# 0_TO_9_Counter_74LS90.net
KiCad netlist of a schematic drawn in EAGLE
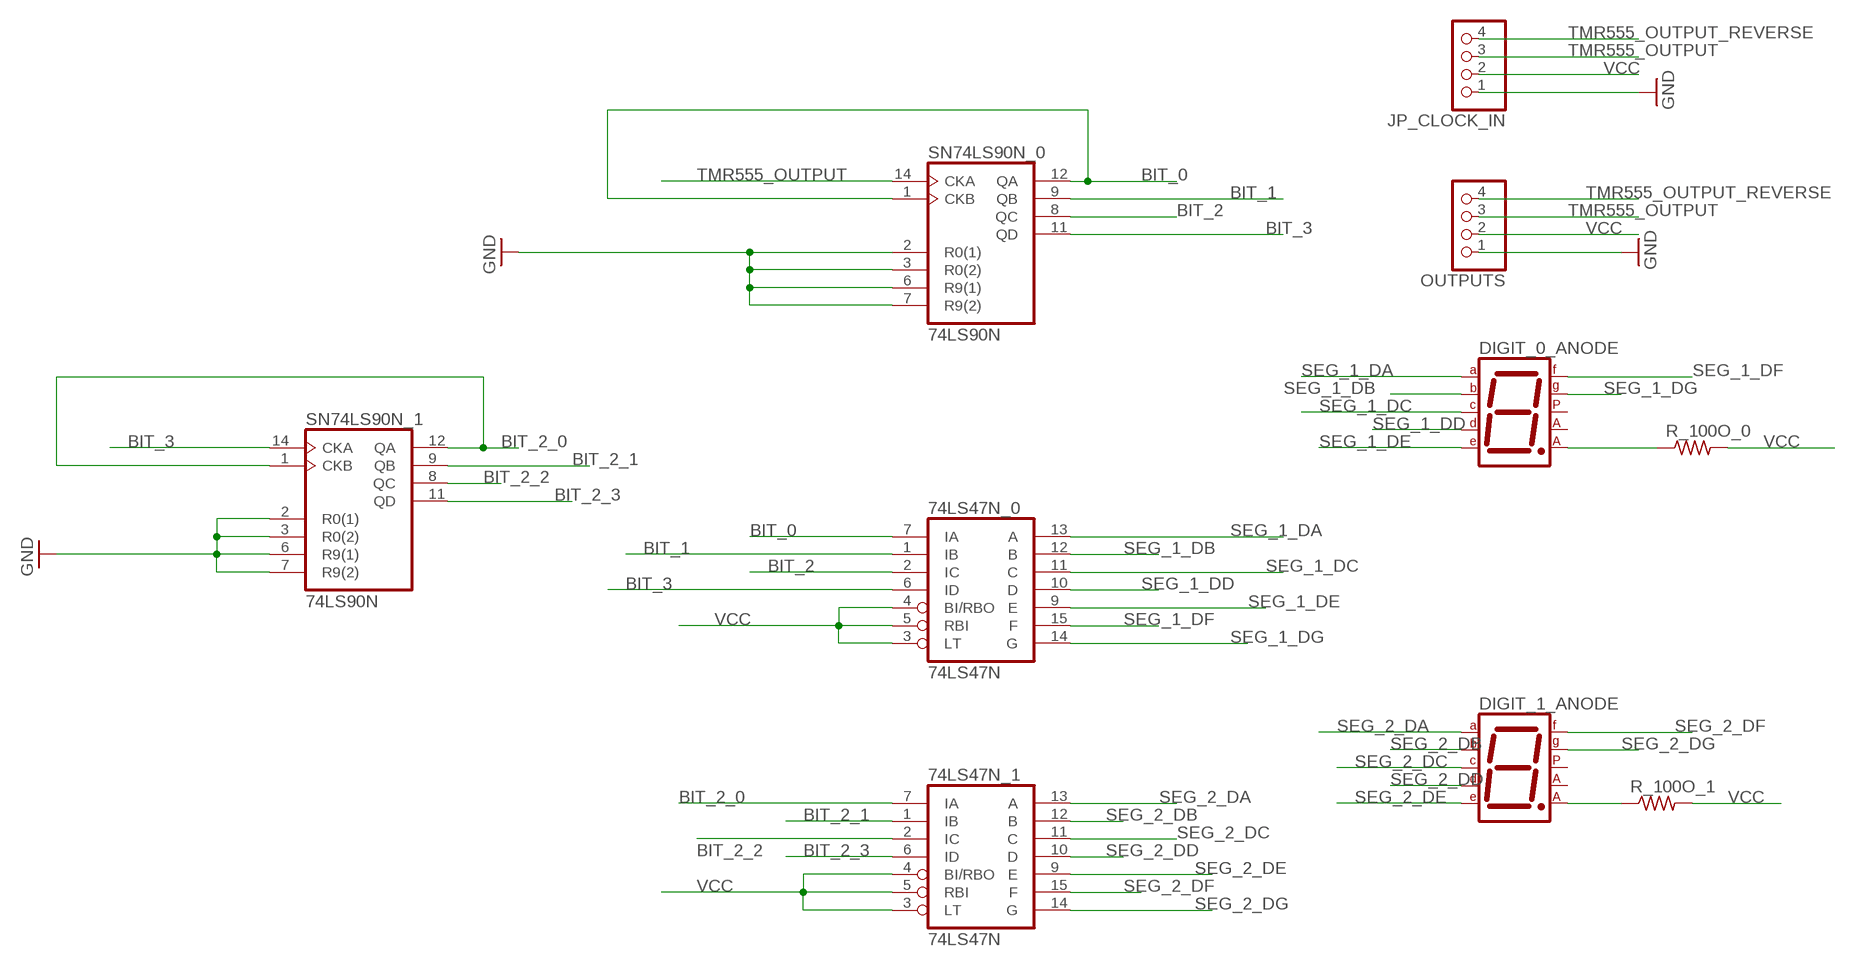
[diagram p0: schematic, sheet 1]

(export (version "E")
  (design (tool "Eeschema 10.0.6"))
  (components
    (comp (ref "74LS47N_0")
      (value "74LS47N")
      (footprint "eagle-import:DIL16")
      (libsource (lib "eagle-import") (part "7447NLS"))
    )
    (comp (ref "74LS47N_1")
      (value "74LS47N")
      (footprint "eagle-import:DIL16")
      (libsource (lib "eagle-import") (part "7447NLS"))
    )
    (comp (ref "DIGIT_0_ANODE")
      (value "7SEG-CA")
      (footprint "eagle-import:7SEG-13")
      (libsource (lib "eagle-import") (part "7SEG-CA"))
    )
    (comp (ref "DIGIT_1_ANODE")
      (value "7SEG-CA")
      (footprint "eagle-import:7SEG-13")
      (libsource (lib "eagle-import") (part "7SEG-CA"))
    )
    (comp (ref "JP_CLOCK_IN")
      (value "PINHD-1X4")
      (footprint "eagle-import:1X04")
      (libsource (lib "eagle-import") (part "PINHD-1X4"))
    )
    (comp (ref "OUTPUTS")
      (value "PINHD-1X4")
      (footprint "eagle-import:1X04")
      (libsource (lib "eagle-import") (part "PINHD-1X4"))
    )
    (comp (ref "R_100O_0")
      (value "R-US_R1206")
      (footprint "eagle-import:R1206")
      (libsource (lib "eagle-import") (part "R-US_R1206"))
    )
    (comp (ref "R_100O_1")
      (value "R-US_R1206")
      (footprint "eagle-import:R1206")
      (libsource (lib "eagle-import") (part "R-US_R1206"))
    )
    (comp (ref "SN74LS90N_0")
      (value "74LS90N")
      (footprint "eagle-import:DIL14")
      (libsource (lib "eagle-import") (part "7490NLS"))
    )
    (comp (ref "SN74LS90N_1")
      (value "74LS90N")
      (footprint "eagle-import:DIL14")
      (libsource (lib "eagle-import") (part "7490NLS"))
    )
  )
  (nets
    (net (code "1") (name "/BIT_0") (class "Default")
      (node (ref "74LS47N_0") (pin "7") (pinfunction "IA_7") (pintype "input"))
      (node (ref "SN74LS90N_0") (pin "1") (pinfunction "CKB_1") (pintype "input"))
      (node (ref "SN74LS90N_0") (pin "12") (pinfunction "QA_12") (pintype "output"))
    )
    (net (code "2") (name "/BIT_1") (class "Default")
      (node (ref "74LS47N_0") (pin "1") (pinfunction "IB_1") (pintype "input"))
      (node (ref "SN74LS90N_0") (pin "9") (pinfunction "QB_9") (pintype "output"))
    )
    (net (code "3") (name "/BIT_2") (class "Default")
      (node (ref "74LS47N_0") (pin "2") (pinfunction "IC_2") (pintype "input"))
      (node (ref "SN74LS90N_0") (pin "8") (pinfunction "QC_8") (pintype "output"))
    )
    (net (code "4") (name "/BIT_2_0") (class "Default")
      (node (ref "74LS47N_1") (pin "7") (pinfunction "IA_7") (pintype "input"))
      (node (ref "SN74LS90N_1") (pin "1") (pinfunction "CKB_1") (pintype "input"))
      (node (ref "SN74LS90N_1") (pin "12") (pinfunction "QA_12") (pintype "output"))
    )
    (net (code "5") (name "/BIT_2_1") (class "Default")
      (node (ref "74LS47N_1") (pin "1") (pinfunction "IB_1") (pintype "input"))
      (node (ref "SN74LS90N_1") (pin "9") (pinfunction "QB_9") (pintype "output"))
    )
    (net (code "6") (name "/BIT_2_2") (class "Default")
      (node (ref "74LS47N_1") (pin "2") (pinfunction "IC_2") (pintype "input"))
      (node (ref "SN74LS90N_1") (pin "8") (pinfunction "QC_8") (pintype "output"))
    )
    (net (code "7") (name "/BIT_2_3") (class "Default")
      (node (ref "74LS47N_1") (pin "6") (pinfunction "ID_6") (pintype "input"))
      (node (ref "SN74LS90N_1") (pin "11") (pinfunction "QD_11") (pintype "output"))
    )
    (net (code "8") (name "/BIT_3") (class "Default")
      (node (ref "74LS47N_0") (pin "6") (pinfunction "ID_6") (pintype "input"))
      (node (ref "SN74LS90N_0") (pin "11") (pinfunction "QD_11") (pintype "output"))
      (node (ref "SN74LS90N_1") (pin "14") (pinfunction "CKA_14") (pintype "input"))
    )
    (net (code "9") (name "/SEG_1_DA") (class "Default")
      (node (ref "74LS47N_0") (pin "13") (pinfunction "A_13") (pintype "output"))
      (node (ref "DIGIT_0_ANODE") (pin "7") (pinfunction "A_7") (pintype "passive"))
    )
    (net (code "10") (name "/SEG_1_DB") (class "Default")
      (node (ref "74LS47N_0") (pin "12") (pinfunction "B_12") (pintype "output"))
      (node (ref "DIGIT_0_ANODE") (pin "6") (pinfunction "B_6") (pintype "passive"))
    )
    (net (code "11") (name "/SEG_1_DC") (class "Default")
      (node (ref "74LS47N_0") (pin "11") (pinfunction "C_11") (pintype "output"))
      (node (ref "DIGIT_0_ANODE") (pin "4") (pinfunction "C_4") (pintype "passive"))
    )
    (net (code "12") (name "/SEG_1_DD") (class "Default")
      (node (ref "74LS47N_0") (pin "10") (pinfunction "D_10") (pintype "output"))
      (node (ref "DIGIT_0_ANODE") (pin "2") (pinfunction "D_2") (pintype "passive"))
    )
    (net (code "13") (name "/SEG_1_DE") (class "Default")
      (node (ref "74LS47N_0") (pin "9") (pinfunction "E_9") (pintype "output"))
      (node (ref "DIGIT_0_ANODE") (pin "1") (pinfunction "E_1") (pintype "passive"))
    )
    (net (code "14") (name "/SEG_1_DF") (class "Default")
      (node (ref "74LS47N_0") (pin "15") (pinfunction "F_15") (pintype "output"))
      (node (ref "DIGIT_0_ANODE") (pin "9") (pinfunction "F_9") (pintype "passive"))
    )
    (net (code "15") (name "/SEG_1_DG") (class "Default")
      (node (ref "74LS47N_0") (pin "14") (pinfunction "G_14") (pintype "output"))
      (node (ref "DIGIT_0_ANODE") (pin "10") (pinfunction "G_10") (pintype "passive"))
    )
    (net (code "16") (name "/SEG_2_DA") (class "Default")
      (node (ref "74LS47N_1") (pin "13") (pinfunction "A_13") (pintype "output"))
      (node (ref "DIGIT_1_ANODE") (pin "7") (pinfunction "A_7") (pintype "passive"))
    )
    (net (code "17") (name "/SEG_2_DB") (class "Default")
      (node (ref "74LS47N_1") (pin "12") (pinfunction "B_12") (pintype "output"))
      (node (ref "DIGIT_1_ANODE") (pin "6") (pinfunction "B_6") (pintype "passive"))
    )
    (net (code "18") (name "/SEG_2_DC") (class "Default")
      (node (ref "74LS47N_1") (pin "11") (pinfunction "C_11") (pintype "output"))
      (node (ref "DIGIT_1_ANODE") (pin "4") (pinfunction "C_4") (pintype "passive"))
    )
    (net (code "19") (name "/SEG_2_DD") (class "Default")
      (node (ref "74LS47N_1") (pin "10") (pinfunction "D_10") (pintype "output"))
      (node (ref "DIGIT_1_ANODE") (pin "2") (pinfunction "D_2") (pintype "passive"))
    )
    (net (code "20") (name "/SEG_2_DE") (class "Default")
      (node (ref "74LS47N_1") (pin "9") (pinfunction "E_9") (pintype "output"))
      (node (ref "DIGIT_1_ANODE") (pin "1") (pinfunction "E_1") (pintype "passive"))
    )
    (net (code "21") (name "/SEG_2_DF") (class "Default")
      (node (ref "74LS47N_1") (pin "15") (pinfunction "F_15") (pintype "output"))
      (node (ref "DIGIT_1_ANODE") (pin "9") (pinfunction "F_9") (pintype "passive"))
    )
    (net (code "22") (name "/SEG_2_DG") (class "Default")
      (node (ref "74LS47N_1") (pin "14") (pinfunction "G_14") (pintype "output"))
      (node (ref "DIGIT_1_ANODE") (pin "10") (pinfunction "G_10") (pintype "passive"))
    )
    (net (code "23") (name "/TMR555_OUTPUT") (class "Default")
      (node (ref "JP_CLOCK_IN") (pin "3") (pinfunction "3_3") (pintype "passive"))
      (node (ref "OUTPUTS") (pin "3") (pinfunction "3_3") (pintype "passive"))
      (node (ref "SN74LS90N_0") (pin "14") (pinfunction "CKA_14") (pintype "input"))
    )
    (net (code "24") (name "/TMR555_OUTPUT_REVERSE") (class "Default")
      (node (ref "JP_CLOCK_IN") (pin "4") (pinfunction "4_4") (pintype "passive"))
      (node (ref "OUTPUTS") (pin "4") (pinfunction "4_4") (pintype "passive"))
    )
    (net (code "25") (name "/VCC") (class "Default")
      (node (ref "74LS47N_0") (pin "3") (pinfunction "LT_3") (pintype "input"))
      (node (ref "74LS47N_0") (pin "4") (pinfunction "BI/RBO_4") (pintype "input"))
      (node (ref "74LS47N_0") (pin "5") (pinfunction "RBI_5") (pintype "input"))
      (node (ref "74LS47N_1") (pin "3") (pinfunction "LT_3") (pintype "input"))
      (node (ref "74LS47N_1") (pin "4") (pinfunction "BI/RBO_4") (pintype "input"))
      (node (ref "74LS47N_1") (pin "5") (pinfunction "RBI_5") (pintype "input"))
      (node (ref "JP_CLOCK_IN") (pin "2") (pinfunction "2_2") (pintype "passive"))
      (node (ref "OUTPUTS") (pin "2") (pinfunction "2_2") (pintype "passive"))
      (node (ref "R_100O_0") (pin "2") (pinfunction "2_2") (pintype "passive"))
      (node (ref "R_100O_1") (pin "2") (pinfunction "2_2") (pintype "passive"))
    )
    (net (code "26") (name "GND") (class "Default")
      (node (ref "JP_CLOCK_IN") (pin "1") (pinfunction "1_1") (pintype "passive"))
      (node (ref "OUTPUTS") (pin "1") (pinfunction "1_1") (pintype "passive"))
      (node (ref "SN74LS90N_0") (pin "2") (pinfunction "R0(1)_2") (pintype "input"))
      (node (ref "SN74LS90N_0") (pin "3") (pinfunction "R0(2)_3") (pintype "input"))
      (node (ref "SN74LS90N_0") (pin "6") (pinfunction "R9(1)_6") (pintype "input"))
      (node (ref "SN74LS90N_0") (pin "7") (pinfunction "R9(2)_7") (pintype "input"))
      (node (ref "SN74LS90N_1") (pin "2") (pinfunction "R0(1)_2") (pintype "input"))
      (node (ref "SN74LS90N_1") (pin "3") (pinfunction "R0(2)_3") (pintype "input"))
      (node (ref "SN74LS90N_1") (pin "6") (pinfunction "R9(1)_6") (pintype "input"))
      (node (ref "SN74LS90N_1") (pin "7") (pinfunction "R9(2)_7") (pintype "input"))
    )
    (net (code "27") (name "Net-(DIGIT_0_ANODE-CA2)") (class "Default")
      (node (ref "DIGIT_0_ANODE") (pin "8") (pinfunction "CA2_8") (pintype "passive"))
      (node (ref "R_100O_0") (pin "1") (pinfunction "1_1") (pintype "passive"))
    )
    (net (code "28") (name "Net-(DIGIT_1_ANODE-CA2)") (class "Default")
      (node (ref "DIGIT_1_ANODE") (pin "8") (pinfunction "CA2_8") (pintype "passive"))
      (node (ref "R_100O_1") (pin "1") (pinfunction "1_1") (pintype "passive"))
    )
    (net (code "29") (name "unconnected-(DIGIT_0_ANODE-CA1-Pad3)") (class "Default")
      (node (ref "DIGIT_0_ANODE") (pin "3") (pinfunction "CA1_3") (pintype "passive"))
    )
    (net (code "30") (name "unconnected-(DIGIT_0_ANODE-DP-Pad5)") (class "Default")
      (node (ref "DIGIT_0_ANODE") (pin "5") (pinfunction "DP_5") (pintype "passive"))
    )
    (net (code "31") (name "unconnected-(DIGIT_1_ANODE-CA1-Pad3)") (class "Default")
      (node (ref "DIGIT_1_ANODE") (pin "3") (pinfunction "CA1_3") (pintype "passive"))
    )
    (net (code "32") (name "unconnected-(DIGIT_1_ANODE-DP-Pad5)") (class "Default")
      (node (ref "DIGIT_1_ANODE") (pin "5") (pinfunction "DP_5") (pintype "passive"))
    )
  )
)
